# LeguinoUno.net
KiCad netlist of a schematic drawn in EAGLE
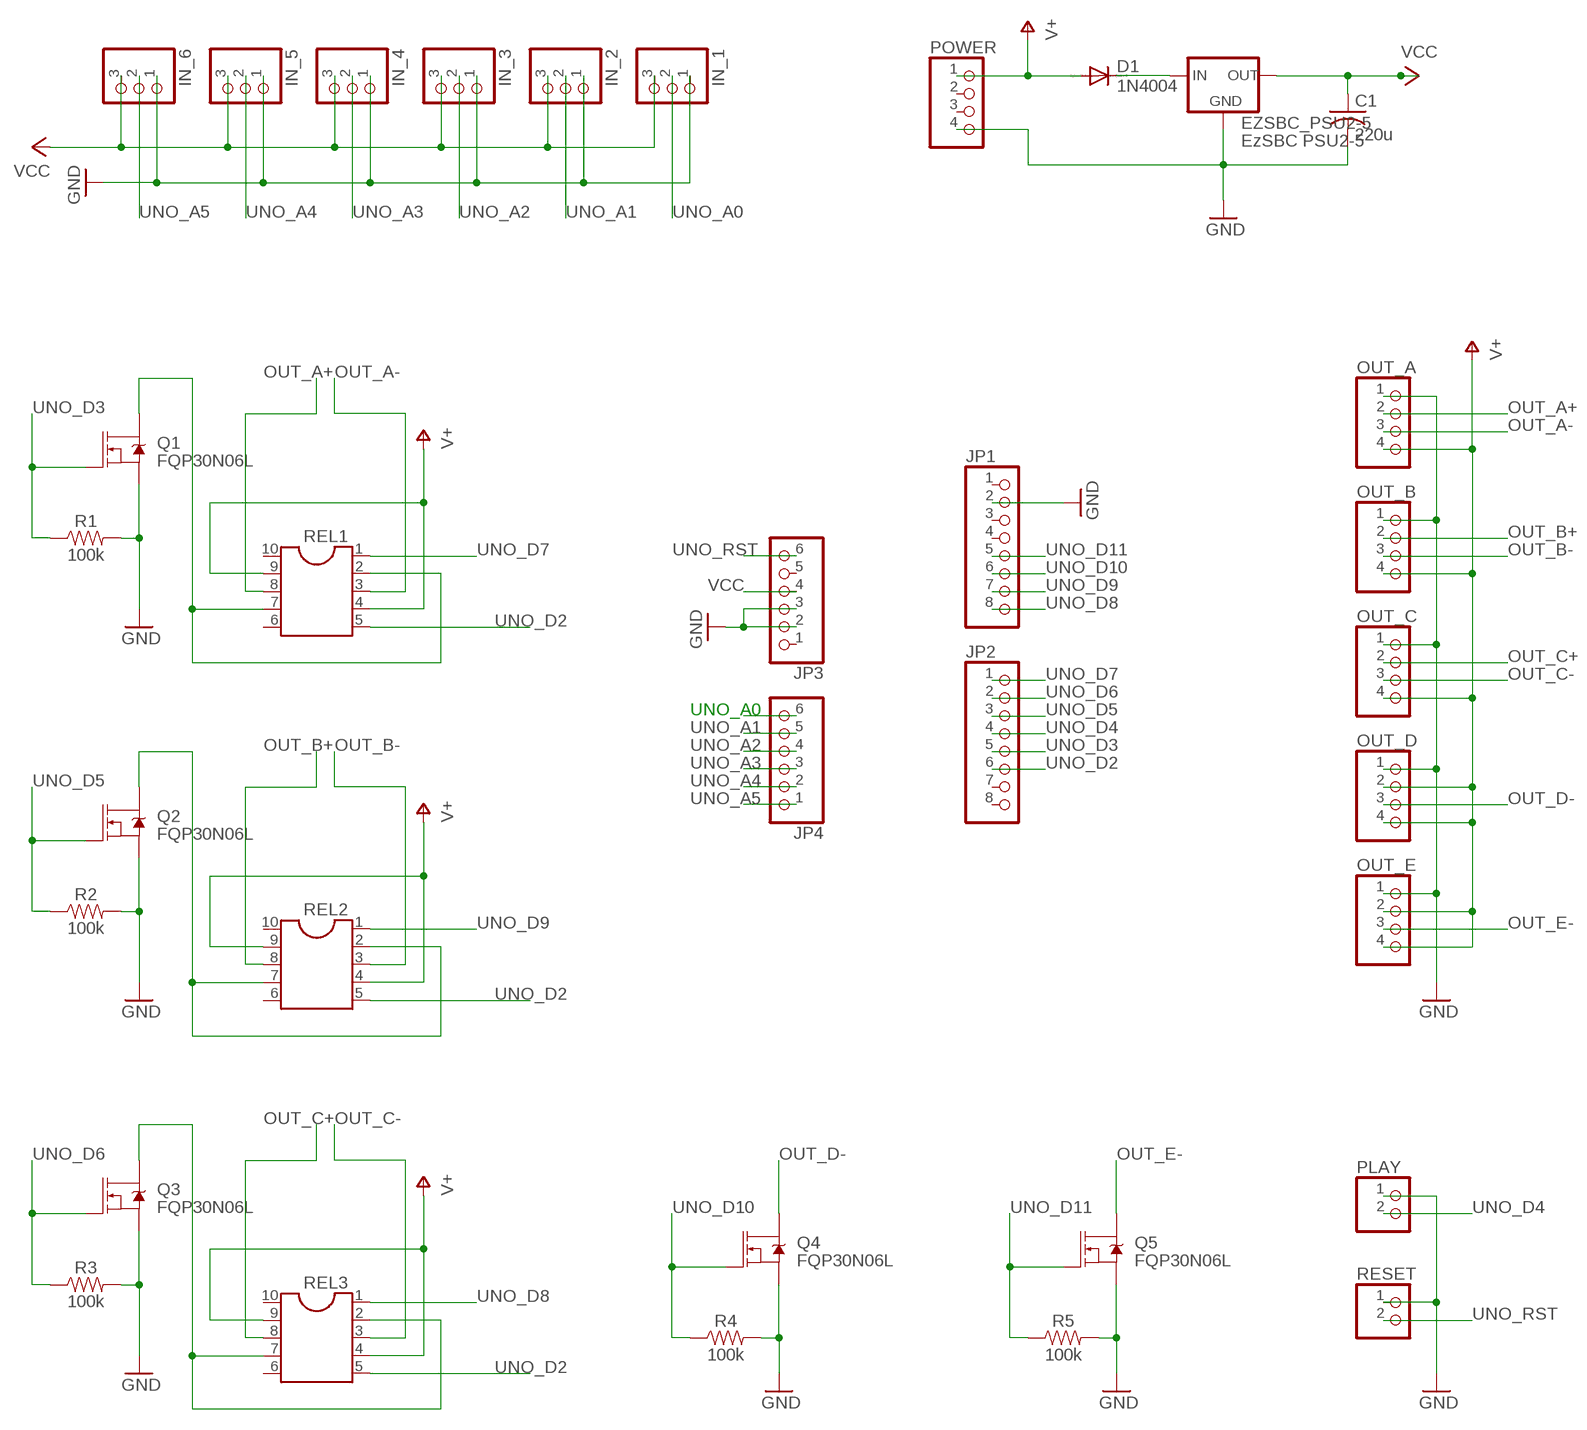
[diagram p0: schematic, sheet 1]

(export (version "E")
  (design (tool "Eeschema 10.0.6"))
  (components
    (comp (ref "C1")
      (value "220u")
      (footprint "eagle-import:C050-030X075")
      (libsource (lib "eagle-import") (part "C-US050-030X075"))
    )
    (comp (ref "D1")
      (value "1N4004")
      (footprint "eagle-import:DO41-10")
      (libsource (lib "eagle-import") (part "1N4004"))
    )
    (comp (ref "EZSBC_PSU2-5")
      (value "EzSBC PSU2-5")
      (footprint "eagle-import:TO-220-ALT")
      (libsource (lib "eagle-import") (part "V_REG_78XX-TO-220"))
    )
    (comp (ref "IN_1")
      (value "PINHD-1X3")
      (footprint "eagle-import:1X03")
      (libsource (lib "eagle-import") (part "PINHD-1X3"))
    )
    (comp (ref "IN_2")
      (value "PINHD-1X3")
      (footprint "eagle-import:1X03")
      (libsource (lib "eagle-import") (part "PINHD-1X3"))
    )
    (comp (ref "IN_3")
      (value "PINHD-1X3")
      (footprint "eagle-import:1X03")
      (libsource (lib "eagle-import") (part "PINHD-1X3"))
    )
    (comp (ref "IN_4")
      (value "PINHD-1X3")
      (footprint "eagle-import:1X03")
      (libsource (lib "eagle-import") (part "PINHD-1X3"))
    )
    (comp (ref "IN_5")
      (value "PINHD-1X3")
      (footprint "eagle-import:1X03")
      (libsource (lib "eagle-import") (part "PINHD-1X3"))
    )
    (comp (ref "IN_6")
      (value "PINHD-1X3")
      (footprint "eagle-import:1X03")
      (libsource (lib "eagle-import") (part "PINHD-1X3"))
    )
    (comp (ref "JP1")
      (value "PINHD-1X8")
      (footprint "eagle-import:1X08")
      (libsource (lib "eagle-import") (part "PINHD-1X8"))
    )
    (comp (ref "JP2")
      (value "PINHD-1X8")
      (footprint "eagle-import:1X08")
      (libsource (lib "eagle-import") (part "PINHD-1X8"))
    )
    (comp (ref "JP3")
      (value "PINHD-1X6")
      (footprint "eagle-import:1X06")
      (libsource (lib "eagle-import") (part "PINHD-1X6"))
    )
    (comp (ref "JP4")
      (value "PINHD-1X6")
      (footprint "eagle-import:1X06")
      (libsource (lib "eagle-import") (part "PINHD-1X6"))
    )
    (comp (ref "OUT_A")
      (value "PINHD-1X4")
      (footprint "eagle-import:1X04")
      (libsource (lib "eagle-import") (part "PINHD-1X4"))
    )
    (comp (ref "OUT_B")
      (value "PINHD-1X4")
      (footprint "eagle-import:1X04")
      (libsource (lib "eagle-import") (part "PINHD-1X4"))
    )
    (comp (ref "OUT_C")
      (value "PINHD-1X4")
      (footprint "eagle-import:1X04")
      (libsource (lib "eagle-import") (part "PINHD-1X4"))
    )
    (comp (ref "OUT_D")
      (value "PINHD-1X4")
      (footprint "eagle-import:1X04")
      (libsource (lib "eagle-import") (part "PINHD-1X4"))
    )
    (comp (ref "OUT_E")
      (value "PINHD-1X4")
      (footprint "eagle-import:1X04")
      (libsource (lib "eagle-import") (part "PINHD-1X4"))
    )
    (comp (ref "PLAY")
      (value "PINHD-1X2")
      (footprint "eagle-import:1X02")
      (libsource (lib "eagle-import") (part "PINHD-1X2"))
    )
    (comp (ref "POWER")
      (value "PINHD-1X4")
      (footprint "eagle-import:1X04")
      (libsource (lib "eagle-import") (part "PINHD-1X4"))
    )
    (comp (ref "Q1")
      (value "FQP30N06L")
      (footprint "eagle-import:TO220V")
      (libsource (lib "eagle-import") (part "MOSFET-NCH-FQP30N06L"))
    )
    (comp (ref "Q2")
      (value "FQP30N06L")
      (footprint "eagle-import:TO220V")
      (libsource (lib "eagle-import") (part "MOSFET-NCH-FQP30N06L"))
    )
    (comp (ref "Q3")
      (value "FQP30N06L")
      (footprint "eagle-import:TO220V")
      (libsource (lib "eagle-import") (part "MOSFET-NCH-FQP30N06L"))
    )
    (comp (ref "Q4")
      (value "FQP30N06L")
      (footprint "eagle-import:TO220V")
      (libsource (lib "eagle-import") (part "MOSFET-NCH-FQP30N06L"))
    )
    (comp (ref "Q5")
      (value "FQP30N06L")
      (footprint "eagle-import:TO220V")
      (libsource (lib "eagle-import") (part "MOSFET-NCH-FQP30N06L"))
    )
    (comp (ref "R1")
      (value "100k")
      (footprint "eagle-import:AXIAL-0.3")
      (libsource (lib "eagle-import") (part "100KOHM-HORIZ-1/4W-1%"))
    )
    (comp (ref "R2")
      (value "100k")
      (footprint "eagle-import:AXIAL-0.3")
      (libsource (lib "eagle-import") (part "100KOHM-HORIZ-1/4W-1%"))
    )
    (comp (ref "R3")
      (value "100k")
      (footprint "eagle-import:AXIAL-0.3")
      (libsource (lib "eagle-import") (part "100KOHM-HORIZ-1/4W-1%"))
    )
    (comp (ref "R4")
      (value "100k")
      (footprint "eagle-import:AXIAL-0.3")
      (libsource (lib "eagle-import") (part "100KOHM-HORIZ-1/4W-1%"))
    )
    (comp (ref "R5")
      (value "100k")
      (footprint "eagle-import:AXIAL-0.3")
      (libsource (lib "eagle-import") (part "100KOHM-HORIZ-1/4W-1%"))
    )
    (comp (ref "REL1")
      (value "DIL10")
      (footprint "eagle-import:DIL10")
      (libsource (lib "eagle-import") (part "DIL10"))
    )
    (comp (ref "REL2")
      (value "DIL10")
      (footprint "eagle-import:DIL10")
      (libsource (lib "eagle-import") (part "DIL10"))
    )
    (comp (ref "REL3")
      (value "DIL10")
      (footprint "eagle-import:DIL10")
      (libsource (lib "eagle-import") (part "DIL10"))
    )
    (comp (ref "RESET")
      (value "PINHD-1X2")
      (footprint "eagle-import:1X02")
      (libsource (lib "eagle-import") (part "PINHD-1X2"))
    )
  )
  (nets
    (net (code "1") (name "/OUT_A+") (class "Default")
      (node (ref "OUT_A") (pin "2") (pinfunction "2_2") (pintype "passive"))
      (node (ref "REL1") (pin "8") (pinfunction "8_8") (pintype "passive"))
    )
    (net (code "2") (name "/OUT_A-") (class "Default")
      (node (ref "OUT_A") (pin "3") (pinfunction "3_3") (pintype "passive"))
      (node (ref "REL1") (pin "3") (pinfunction "3_3") (pintype "passive"))
    )
    (net (code "3") (name "/OUT_B+") (class "Default")
      (node (ref "OUT_B") (pin "2") (pinfunction "2_2") (pintype "passive"))
      (node (ref "REL2") (pin "8") (pinfunction "8_8") (pintype "passive"))
    )
    (net (code "4") (name "/OUT_B-") (class "Default")
      (node (ref "OUT_B") (pin "3") (pinfunction "3_3") (pintype "passive"))
      (node (ref "REL2") (pin "3") (pinfunction "3_3") (pintype "passive"))
    )
    (net (code "5") (name "/OUT_C+") (class "Default")
      (node (ref "OUT_C") (pin "2") (pinfunction "2_2") (pintype "passive"))
      (node (ref "REL3") (pin "8") (pinfunction "8_8") (pintype "passive"))
    )
    (net (code "6") (name "/OUT_C-") (class "Default")
      (node (ref "OUT_C") (pin "3") (pinfunction "3_3") (pintype "passive"))
      (node (ref "REL3") (pin "3") (pinfunction "3_3") (pintype "passive"))
    )
    (net (code "7") (name "/OUT_D-") (class "Default")
      (node (ref "OUT_D") (pin "3") (pinfunction "3_3") (pintype "passive"))
      (node (ref "Q4") (pin "2") (pinfunction "D_2") (pintype "bidirectional"))
    )
    (net (code "8") (name "/OUT_E-") (class "Default")
      (node (ref "OUT_E") (pin "3") (pinfunction "3_3") (pintype "passive"))
      (node (ref "Q5") (pin "2") (pinfunction "D_2") (pintype "bidirectional"))
    )
    (net (code "9") (name "/UNO_A0") (class "Default")
      (node (ref "IN_1") (pin "2") (pinfunction "2_2") (pintype "passive"))
      (node (ref "JP4") (pin "6") (pinfunction "6_6") (pintype "passive"))
    )
    (net (code "10") (name "/UNO_A1") (class "Default")
      (node (ref "IN_2") (pin "2") (pinfunction "2_2") (pintype "passive"))
      (node (ref "JP4") (pin "5") (pinfunction "5_5") (pintype "passive"))
    )
    (net (code "11") (name "/UNO_A2") (class "Default")
      (node (ref "IN_3") (pin "2") (pinfunction "2_2") (pintype "passive"))
      (node (ref "JP4") (pin "4") (pinfunction "4_4") (pintype "passive"))
    )
    (net (code "12") (name "/UNO_A3") (class "Default")
      (node (ref "IN_4") (pin "2") (pinfunction "2_2") (pintype "passive"))
      (node (ref "JP4") (pin "3") (pinfunction "3_3") (pintype "passive"))
    )
    (net (code "13") (name "/UNO_A4") (class "Default")
      (node (ref "IN_5") (pin "2") (pinfunction "2_2") (pintype "passive"))
      (node (ref "JP4") (pin "2") (pinfunction "2_2") (pintype "passive"))
    )
    (net (code "14") (name "/UNO_A5") (class "Default")
      (node (ref "IN_6") (pin "2") (pinfunction "2_2") (pintype "passive"))
      (node (ref "JP4") (pin "1") (pinfunction "1_1") (pintype "passive"))
    )
    (net (code "15") (name "/UNO_D2") (class "Default")
      (node (ref "JP2") (pin "6") (pinfunction "6_6") (pintype "passive"))
      (node (ref "REL1") (pin "5") (pinfunction "5_5") (pintype "passive"))
      (node (ref "REL2") (pin "5") (pinfunction "5_5") (pintype "passive"))
      (node (ref "REL3") (pin "5") (pinfunction "5_5") (pintype "passive"))
    )
    (net (code "16") (name "/UNO_D3") (class "Default")
      (node (ref "JP2") (pin "5") (pinfunction "5_5") (pintype "passive"))
      (node (ref "Q1") (pin "1") (pinfunction "G_1") (pintype "bidirectional"))
      (node (ref "R1") (pin "P$1") (pinfunction "1_P$1") (pintype "passive"))
    )
    (net (code "17") (name "/UNO_D4") (class "Default")
      (node (ref "JP2") (pin "4") (pinfunction "4_4") (pintype "passive"))
      (node (ref "PLAY") (pin "2") (pinfunction "2_2") (pintype "passive"))
    )
    (net (code "18") (name "/UNO_D5") (class "Default")
      (node (ref "JP2") (pin "3") (pinfunction "3_3") (pintype "passive"))
      (node (ref "Q2") (pin "1") (pinfunction "G_1") (pintype "bidirectional"))
      (node (ref "R2") (pin "P$1") (pinfunction "1_P$1") (pintype "passive"))
    )
    (net (code "19") (name "/UNO_D6") (class "Default")
      (node (ref "JP2") (pin "2") (pinfunction "2_2") (pintype "passive"))
      (node (ref "Q3") (pin "1") (pinfunction "G_1") (pintype "bidirectional"))
      (node (ref "R3") (pin "P$1") (pinfunction "1_P$1") (pintype "passive"))
    )
    (net (code "20") (name "/UNO_D7") (class "Default")
      (node (ref "JP2") (pin "1") (pinfunction "1_1") (pintype "passive"))
      (node (ref "REL1") (pin "1") (pinfunction "1_1") (pintype "passive"))
    )
    (net (code "21") (name "/UNO_D8") (class "Default")
      (node (ref "JP1") (pin "8") (pinfunction "8_8") (pintype "passive"))
      (node (ref "REL3") (pin "1") (pinfunction "1_1") (pintype "passive"))
    )
    (net (code "22") (name "/UNO_D9") (class "Default")
      (node (ref "JP1") (pin "7") (pinfunction "7_7") (pintype "passive"))
      (node (ref "REL2") (pin "1") (pinfunction "1_1") (pintype "passive"))
    )
    (net (code "23") (name "/UNO_D10") (class "Default")
      (node (ref "JP1") (pin "6") (pinfunction "6_6") (pintype "passive"))
      (node (ref "Q4") (pin "1") (pinfunction "G_1") (pintype "bidirectional"))
      (node (ref "R4") (pin "P$1") (pinfunction "1_P$1") (pintype "passive"))
    )
    (net (code "24") (name "/UNO_D11") (class "Default")
      (node (ref "JP1") (pin "5") (pinfunction "5_5") (pintype "passive"))
      (node (ref "Q5") (pin "1") (pinfunction "G_1") (pintype "bidirectional"))
      (node (ref "R5") (pin "P$1") (pinfunction "1_P$1") (pintype "passive"))
    )
    (net (code "25") (name "/UNO_RST") (class "Default")
      (node (ref "JP3") (pin "6") (pinfunction "6_6") (pintype "passive"))
      (node (ref "RESET") (pin "2") (pinfunction "2_2") (pintype "passive"))
    )
    (net (code "26") (name "GND") (class "Default")
      (node (ref "C1") (pin "2") (pinfunction "2_2") (pintype "passive"))
      (node (ref "EZSBC_PSU2-5") (pin "GND") (pinfunction "GND_GND") (pintype "input"))
      (node (ref "IN_1") (pin "1") (pinfunction "1_1") (pintype "passive"))
      (node (ref "IN_2") (pin "1") (pinfunction "1_1") (pintype "passive"))
      (node (ref "IN_3") (pin "1") (pinfunction "1_1") (pintype "passive"))
      (node (ref "IN_4") (pin "1") (pinfunction "1_1") (pintype "passive"))
      (node (ref "IN_5") (pin "1") (pinfunction "1_1") (pintype "passive"))
      (node (ref "IN_6") (pin "1") (pinfunction "1_1") (pintype "passive"))
      (node (ref "JP1") (pin "2") (pinfunction "2_2") (pintype "passive"))
      (node (ref "JP3") (pin "2") (pinfunction "2_2") (pintype "passive"))
      (node (ref "JP3") (pin "3") (pinfunction "3_3") (pintype "passive"))
      (node (ref "OUT_A") (pin "1") (pinfunction "1_1") (pintype "passive"))
      (node (ref "OUT_B") (pin "1") (pinfunction "1_1") (pintype "passive"))
      (node (ref "OUT_C") (pin "1") (pinfunction "1_1") (pintype "passive"))
      (node (ref "OUT_D") (pin "1") (pinfunction "1_1") (pintype "passive"))
      (node (ref "OUT_E") (pin "1") (pinfunction "1_1") (pintype "passive"))
      (node (ref "PLAY") (pin "1") (pinfunction "1_1") (pintype "passive"))
      (node (ref "POWER") (pin "4") (pinfunction "4_4") (pintype "passive"))
      (node (ref "Q1") (pin "3") (pinfunction "S_3") (pintype "bidirectional"))
      (node (ref "Q2") (pin "3") (pinfunction "S_3") (pintype "bidirectional"))
      (node (ref "Q3") (pin "3") (pinfunction "S_3") (pintype "bidirectional"))
      (node (ref "Q4") (pin "3") (pinfunction "S_3") (pintype "bidirectional"))
      (node (ref "Q5") (pin "3") (pinfunction "S_3") (pintype "bidirectional"))
      (node (ref "R1") (pin "P$2") (pinfunction "2_P$2") (pintype "passive"))
      (node (ref "R2") (pin "P$2") (pinfunction "2_P$2") (pintype "passive"))
      (node (ref "R3") (pin "P$2") (pinfunction "2_P$2") (pintype "passive"))
      (node (ref "R4") (pin "P$2") (pinfunction "2_P$2") (pintype "passive"))
      (node (ref "R5") (pin "P$2") (pinfunction "2_P$2") (pintype "passive"))
      (node (ref "RESET") (pin "1") (pinfunction "1_1") (pintype "passive"))
    )
    (net (code "27") (name "Net-(D1-PadC)") (class "Default")
      (node (ref "D1") (pin "C") (pinfunction "C_C") (pintype "passive"))
      (node (ref "EZSBC_PSU2-5") (pin "IN") (pinfunction "IN_IN") (pintype "input"))
    )
    (net (code "28") (name "Net-(Q1-D)") (class "Default")
      (node (ref "Q1") (pin "2") (pinfunction "D_2") (pintype "bidirectional"))
      (node (ref "REL1") (pin "2") (pinfunction "2_2") (pintype "passive"))
      (node (ref "REL1") (pin "7") (pinfunction "7_7") (pintype "passive"))
    )
    (net (code "29") (name "Net-(Q2-D)") (class "Default")
      (node (ref "Q2") (pin "2") (pinfunction "D_2") (pintype "bidirectional"))
      (node (ref "REL2") (pin "2") (pinfunction "2_2") (pintype "passive"))
      (node (ref "REL2") (pin "7") (pinfunction "7_7") (pintype "passive"))
    )
    (net (code "30") (name "Net-(Q3-D)") (class "Default")
      (node (ref "Q3") (pin "2") (pinfunction "D_2") (pintype "bidirectional"))
      (node (ref "REL3") (pin "2") (pinfunction "2_2") (pintype "passive"))
      (node (ref "REL3") (pin "7") (pinfunction "7_7") (pintype "passive"))
    )
    (net (code "31") (name "V+") (class "Default")
      (node (ref "D1") (pin "A") (pinfunction "A_A") (pintype "passive"))
      (node (ref "OUT_A") (pin "4") (pinfunction "4_4") (pintype "passive"))
      (node (ref "OUT_B") (pin "4") (pinfunction "4_4") (pintype "passive"))
      (node (ref "OUT_C") (pin "4") (pinfunction "4_4") (pintype "passive"))
      (node (ref "OUT_D") (pin "2") (pinfunction "2_2") (pintype "passive"))
      (node (ref "OUT_D") (pin "4") (pinfunction "4_4") (pintype "passive"))
      (node (ref "OUT_E") (pin "2") (pinfunction "2_2") (pintype "passive"))
      (node (ref "OUT_E") (pin "4") (pinfunction "4_4") (pintype "passive"))
      (node (ref "POWER") (pin "1") (pinfunction "1_1") (pintype "passive"))
      (node (ref "REL1") (pin "4") (pinfunction "4_4") (pintype "passive"))
      (node (ref "REL1") (pin "9") (pinfunction "9_9") (pintype "passive"))
      (node (ref "REL2") (pin "4") (pinfunction "4_4") (pintype "passive"))
      (node (ref "REL2") (pin "9") (pinfunction "9_9") (pintype "passive"))
      (node (ref "REL3") (pin "4") (pinfunction "4_4") (pintype "passive"))
      (node (ref "REL3") (pin "9") (pinfunction "9_9") (pintype "passive"))
    )
    (net (code "32") (name "VCC") (class "Default")
      (node (ref "C1") (pin "1") (pinfunction "1_1") (pintype "passive"))
      (node (ref "EZSBC_PSU2-5") (pin "OUT") (pinfunction "OUT_OUT") (pintype "passive"))
      (node (ref "IN_1") (pin "3") (pinfunction "3_3") (pintype "passive"))
      (node (ref "IN_2") (pin "3") (pinfunction "3_3") (pintype "passive"))
      (node (ref "IN_3") (pin "3") (pinfunction "3_3") (pintype "passive"))
      (node (ref "IN_4") (pin "3") (pinfunction "3_3") (pintype "passive"))
      (node (ref "IN_5") (pin "3") (pinfunction "3_3") (pintype "passive"))
      (node (ref "IN_6") (pin "3") (pinfunction "3_3") (pintype "passive"))
      (node (ref "JP3") (pin "4") (pinfunction "4_4") (pintype "passive"))
    )
    (net (code "33") (name "unconnected-(JP1-Pad1)") (class "Default")
      (node (ref "JP1") (pin "1") (pinfunction "1_1") (pintype "passive"))
    )
    (net (code "34") (name "unconnected-(JP1-Pad3)") (class "Default")
      (node (ref "JP1") (pin "3") (pinfunction "3_3") (pintype "passive"))
    )
    (net (code "35") (name "unconnected-(JP1-Pad4)") (class "Default")
      (node (ref "JP1") (pin "4") (pinfunction "4_4") (pintype "passive"))
    )
    (net (code "36") (name "unconnected-(JP2-Pad7)") (class "Default")
      (node (ref "JP2") (pin "7") (pinfunction "7_7") (pintype "passive"))
    )
    (net (code "37") (name "unconnected-(JP2-Pad8)") (class "Default")
      (node (ref "JP2") (pin "8") (pinfunction "8_8") (pintype "passive"))
    )
    (net (code "38") (name "unconnected-(JP3-Pad1)") (class "Default")
      (node (ref "JP3") (pin "1") (pinfunction "1_1") (pintype "passive"))
    )
    (net (code "39") (name "unconnected-(JP3-Pad5)") (class "Default")
      (node (ref "JP3") (pin "5") (pinfunction "5_5") (pintype "passive"))
    )
    (net (code "40") (name "unconnected-(POWER-Pad2)") (class "Default")
      (node (ref "POWER") (pin "2") (pinfunction "2_2") (pintype "passive"))
    )
    (net (code "41") (name "unconnected-(POWER-Pad3)") (class "Default")
      (node (ref "POWER") (pin "3") (pinfunction "3_3") (pintype "passive"))
    )
    (net (code "42") (name "unconnected-(REL1-Pad6)") (class "Default")
      (node (ref "REL1") (pin "6") (pinfunction "6_6") (pintype "passive"))
    )
    (net (code "43") (name "unconnected-(REL1-Pad10)") (class "Default")
      (node (ref "REL1") (pin "10") (pinfunction "10_10") (pintype "passive"))
    )
    (net (code "44") (name "unconnected-(REL2-Pad6)") (class "Default")
      (node (ref "REL2") (pin "6") (pinfunction "6_6") (pintype "passive"))
    )
    (net (code "45") (name "unconnected-(REL2-Pad10)") (class "Default")
      (node (ref "REL2") (pin "10") (pinfunction "10_10") (pintype "passive"))
    )
    (net (code "46") (name "unconnected-(REL3-Pad6)") (class "Default")
      (node (ref "REL3") (pin "6") (pinfunction "6_6") (pintype "passive"))
    )
    (net (code "47") (name "unconnected-(REL3-Pad10)") (class "Default")
      (node (ref "REL3") (pin "10") (pinfunction "10_10") (pintype "passive"))
    )
  )
)
